# V01.net
KiCad netlist of a schematic drawn in Altium Designer
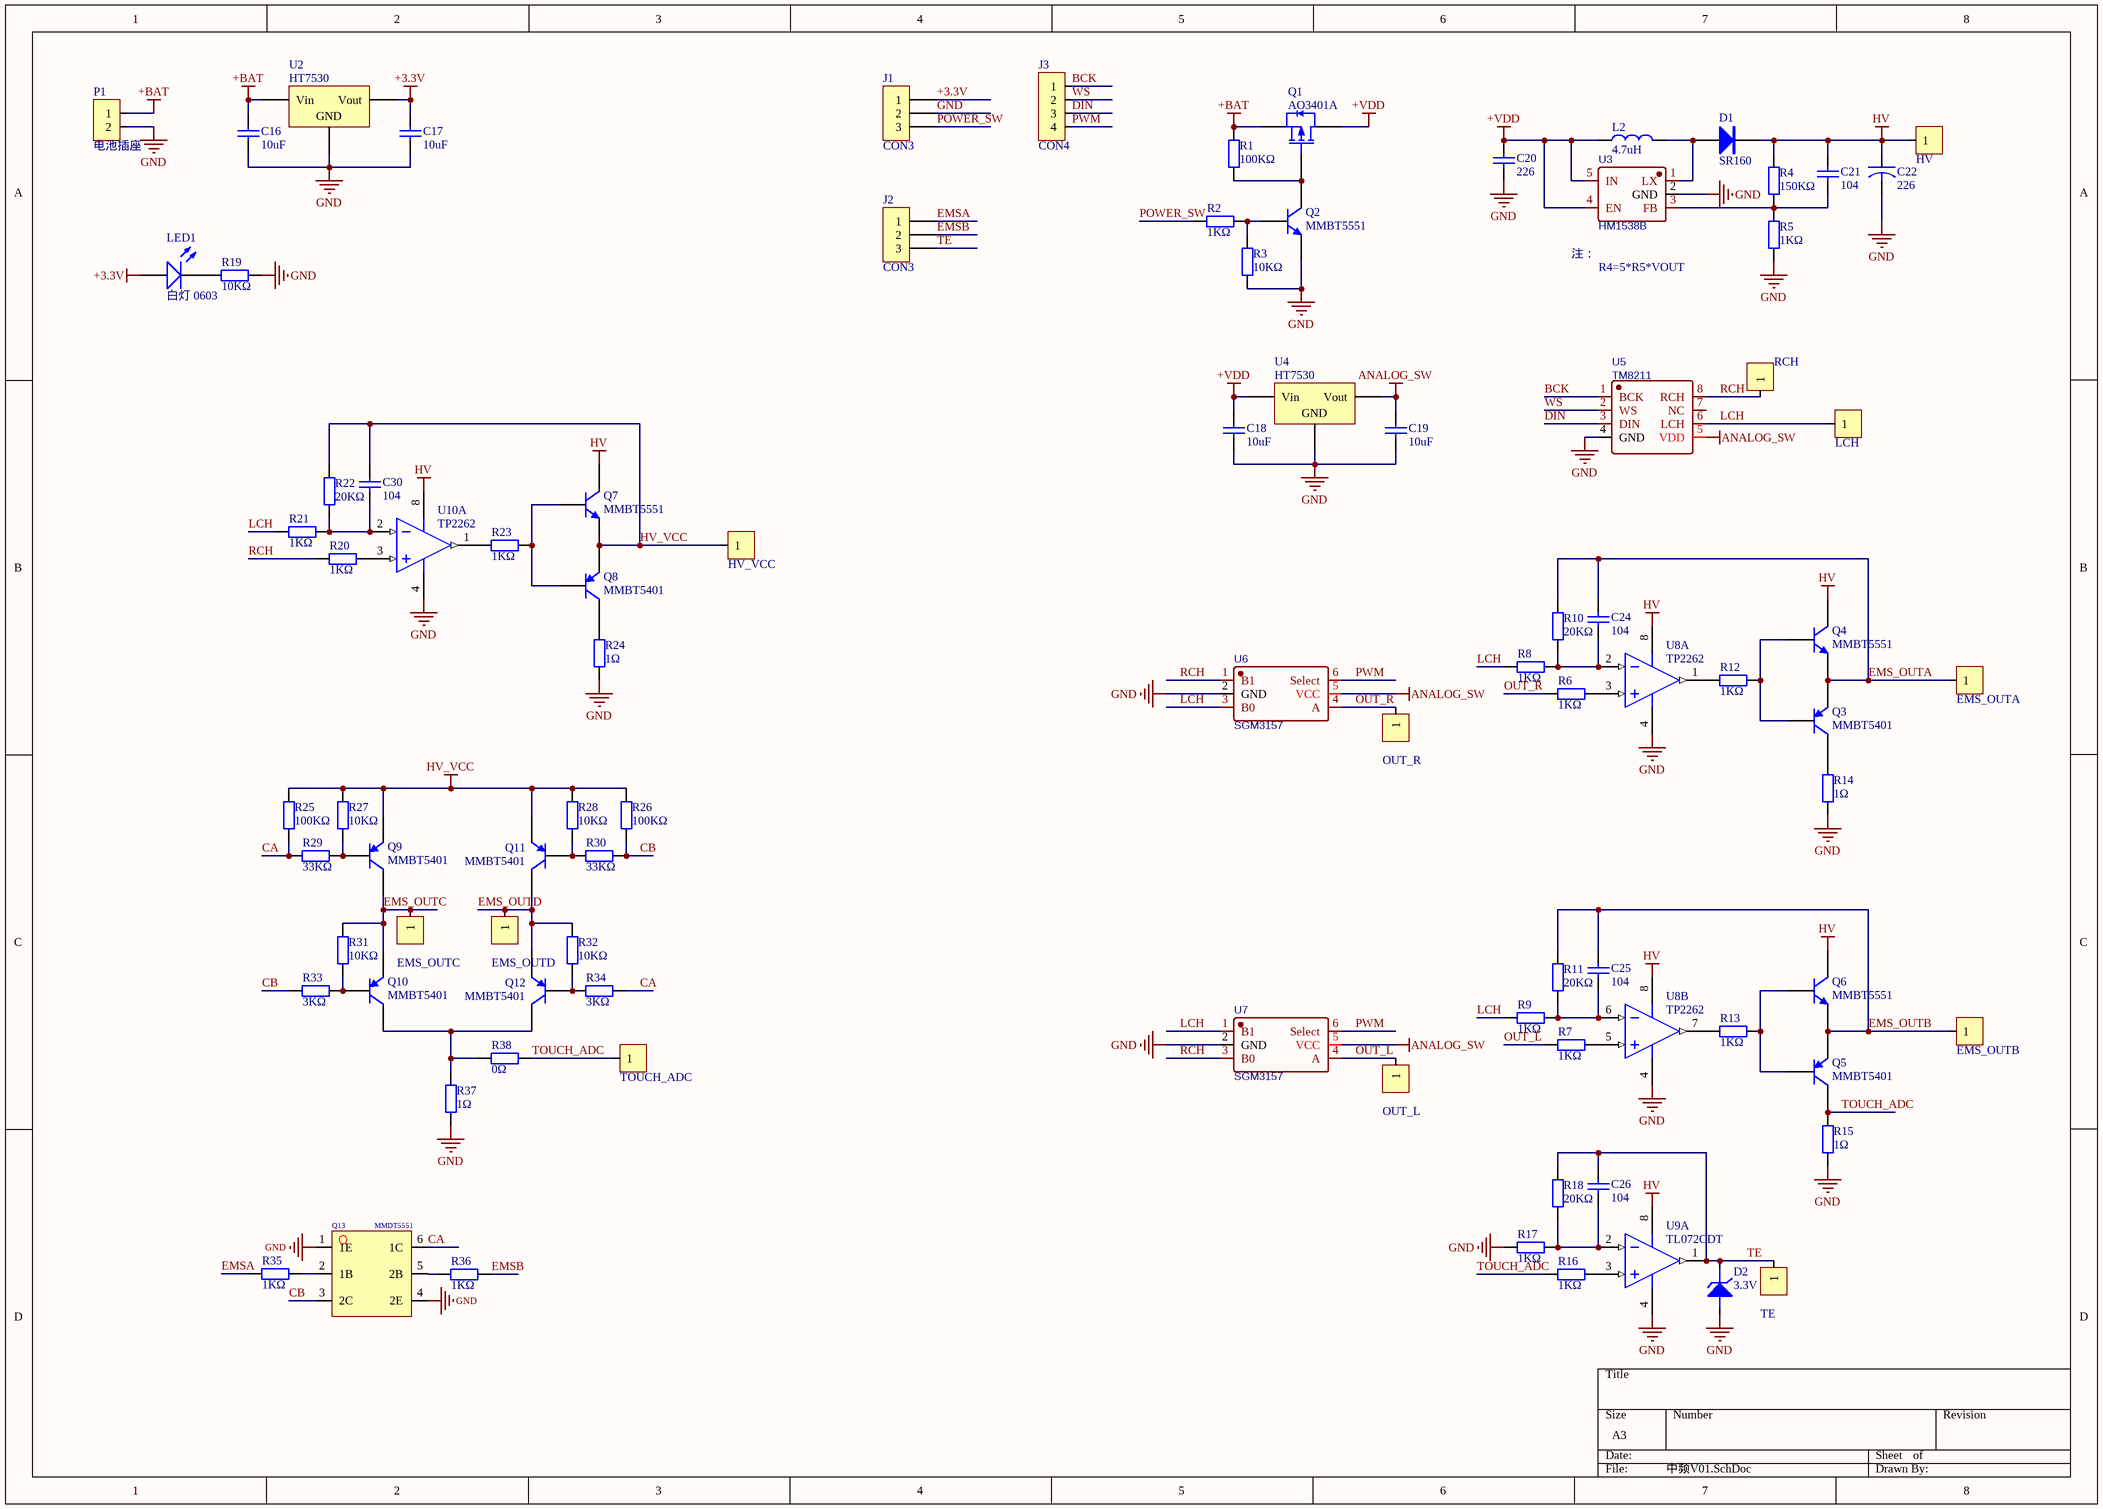
[diagram p0: 中频V01.SchDoc]

(export (version "E")
  (design (tool "Eeschema 10.0.6"))
  (components
    (comp (ref "C16")
      (value "10uF")
      (footprint "0603_C")
      (description "贴片电容")
      (libsource (lib "Cap") (part "0603 1.2nF (122) 10% 50V"))
    )
    (comp (ref "C17")
      (value "10uF")
      (footprint "0603_C")
      (description "贴片电容")
      (libsource (lib "Cap") (part "0603 1.2nF (122) 10% 50V"))
    )
    (comp (ref "C18")
      (value "10uF")
      (footprint "0603_C")
      (description "贴片电容")
      (libsource (lib "Cap") (part "0603 1.2nF (122) 10% 50V"))
    )
    (comp (ref "C19")
      (value "10uF")
      (footprint "0603_C")
      (description "贴片电容")
      (libsource (lib "Cap") (part "0603 1.2nF (122) 10% 50V"))
    )
    (comp (ref "C20")
      (value "226")
      (footprint "0603_C")
      (description "贴片电容")
      (libsource (lib "Cap") (part "0603 1uF (105) 10% 50V"))
    )
    (comp (ref "C21")
      (value "104")
      (footprint "0603_C")
      (description "贴片电容")
      (libsource (lib "Cap") (part "0603 1uF (105) 10% 50V"))
    )
    (comp (ref "C22")
      (value "226")
      (footprint "1206_C")
      (description "Capacitor")
      (libsource (lib "原理图标准元件库") (part "CAPACITOR"))
    )
    (comp (ref "C24")
      (value "104")
      (footprint "0603_C")
      (description "贴片电容")
      (libsource (lib "Cap") (part "0603 1.2nF (122) 10% 50V"))
    )
    (comp (ref "C25")
      (value "104")
      (footprint "0603_C")
      (description "贴片电容")
      (libsource (lib "Cap") (part "0603 1.2nF (122) 10% 50V"))
    )
    (comp (ref "C26")
      (value "104")
      (footprint "0603_C")
      (description "贴片电容")
      (libsource (lib "Cap") (part "0603 1.2nF (122) 10% 50V"))
    )
    (comp (ref "C30")
      (value "104")
      (footprint "0603_C")
      (description "贴片电容")
      (libsource (lib "Cap") (part "0603 1.2nF (122) 10% 50V"))
    )
    (comp (ref "D1") (value "SR160") (footprint "SOD-123") (libsource (lib "XIONG190817") (part "DO")))
    (comp (ref "D2")
      (value "3.3V")
      (footprint "SOD-323")
      (description "Zener Diode")
      (libsource (lib "原理图标准元件库") (part "ZENER3"))
    )
    (comp (ref "EMS_OUTA")
      (value "CON1")
      (footprint "PAD-1P")
      (description "Connector")
      (libsource (lib "") (part "CON1_1"))
    )
    (comp (ref "EMS_OUTB")
      (value "CON1")
      (footprint "PAD-1P")
      (description "Connector")
      (libsource (lib "") (part "CON1_1"))
    )
    (comp (ref "EMS_OUTC")
      (value "CON1")
      (footprint "PAD-1P")
      (description "Connector")
      (libsource (lib "原理图标准元件库") (part "CON1"))
    )
    (comp (ref "EMS_OUTD")
      (value "CON1")
      (footprint "PAD-1P")
      (description "Connector")
      (libsource (lib "原理图标准元件库") (part "CON1"))
    )
    (comp (ref "HV")
      (value "CON1")
      (footprint "PAD-1P")
      (description "Connector")
      (libsource (lib "") (part "CON1_1"))
    )
    (comp (ref "HV_VCC")
      (value "CON1")
      (footprint "PAD-1P")
      (description "Connector")
      (libsource (lib "") (part "CON1_1"))
    )
    (comp (ref "J1")
      (value "CON3")
      (footprint "HDR-TH_3P-P2.54-V")
      (description "Connector")
      (libsource (lib "原理图标准元件库") (part "CON3"))
    )
    (comp (ref "J2")
      (value "CON3")
      (footprint "HDR-TH_3P-P2.54-V")
      (description "Connector")
      (libsource (lib "原理图标准元件库") (part "CON3"))
    )
    (comp (ref "J3")
      (value "CON4")
      (footprint "HDR-TH_4P-P2.54-V")
      (description "Connector")
      (libsource (lib "原理图标准元件库") (part "CON4"))
    )
    (comp (ref "L2") (value "4.7uH") (footprint "CD43") (libsource (lib "XIONG190817") (part "INDUCTOR")))
    (comp (ref "LCH")
      (value "CON1")
      (footprint "PAD-1P")
      (description "Connector")
      (libsource (lib "") (part "CON1_1"))
    )
    (comp (ref "LED1")
      (value "白灯 0603")
      (footprint "0603_LED_S1")
      (description "发光二极管")
      (libsource (lib "LED") (part "0603 白灯"))
    )
    (comp (ref "OUT_L")
      (value "CON1")
      (footprint "PAD-1P")
      (description "Connector")
      (libsource (lib "原理图标准元件库") (part "CON1"))
    )
    (comp (ref "OUT_R")
      (value "CON1")
      (footprint "PAD-1P")
      (description "Connector")
      (libsource (lib "原理图标准元件库") (part "CON1"))
    )
    (comp (ref "P1")
      (value "电池插座")
      (footprint "1.25-2PIN")
      (description "Connector")
      (libsource (lib "原理图标准元件库") (part "CON2"))
    )
    (comp (ref "Q1")
      (value "AO3401A")
      (footprint "SOT-23-3L")
      (description "MOS(场效应管)")
      (libsource (lib "MOS") (part "AO3401A P道沟 X13A15 SOT-23"))
    )
    (comp (ref "Q2")
      (value "MMBT5551")
      (footprint "SOT-23(SOT-23-3)")
      (description "三极管")
      (libsource (lib "Transistor_NPN") (part "SOT-23 MMBT5551  G1"))
    )
    (comp (ref "Q3")
      (value "MMBT5401")
      (footprint "SOT-23(SOT-23-3)")
      (description "三极管")
      (libsource (lib "Transistor_PNP") (part "SOT-23 MMBT5401 2L"))
    )
    (comp (ref "Q4")
      (value "MMBT5551")
      (footprint "SOT-23(SOT-23-3)")
      (description "三极管")
      (libsource (lib "Transistor_NPN") (part "SOT-23 MMBT5551  G1"))
    )
    (comp (ref "Q5")
      (value "MMBT5401")
      (footprint "SOT-23(SOT-23-3)")
      (description "三极管")
      (libsource (lib "Transistor_PNP") (part "SOT-23 MMBT5401 2L"))
    )
    (comp (ref "Q6")
      (value "MMBT5551")
      (footprint "SOT-23(SOT-23-3)")
      (description "三极管")
      (libsource (lib "Transistor_NPN") (part "SOT-23 MMBT5551  G1"))
    )
    (comp (ref "Q7")
      (value "MMBT5551")
      (footprint "SOT-23(SOT-23-3)")
      (description "三极管")
      (libsource (lib "Transistor_NPN") (part "SOT-23 MMBT5551  G1"))
    )
    (comp (ref "Q8")
      (value "MMBT5401")
      (footprint "SOT-23(SOT-23-3)")
      (description "三极管")
      (libsource (lib "Transistor_PNP") (part "SOT-23 MMBT5401 2L"))
    )
    (comp (ref "Q9")
      (value "MMBT5401")
      (footprint "SOT-23(SOT-23-3)")
      (description "三极管")
      (libsource (lib "Transistor_PNP") (part "SOT-23 MMBT5401 2L"))
    )
    (comp (ref "Q10")
      (value "MMBT5401")
      (footprint "SOT-23(SOT-23-3)")
      (description "三极管")
      (libsource (lib "Transistor_PNP") (part "SOT-23 MMBT5401 2L"))
    )
    (comp (ref "Q11")
      (value "MMBT5401")
      (footprint "SOT-23(SOT-23-3)")
      (description "三极管")
      (libsource (lib "Transistor_PNP") (part "SOT-23 MMBT5401 2L"))
    )
    (comp (ref "Q12")
      (value "MMBT5401")
      (footprint "SOT-23(SOT-23-3)")
      (description "三极管")
      (libsource (lib "Transistor_PNP") (part "SOT-23 MMBT5401 2L"))
    )
    (comp (ref "Q13") (value "MMDT5551") (footprint "SOT-363") (libsource (lib "宋德一自画库") (part "MMDT5551")))
    (comp (ref "R1")
      (value "100KΩ")
      (footprint "0603_R")
      (description "贴片电阻")
      (libsource (lib "") (part "0603 1.2KΩ (1201) 1%_3"))
    )
    (comp (ref "R2")
      (value "1KΩ")
      (footprint "0603_R")
      (description "贴片电阻")
      (libsource (lib "") (part "0603 1.2KΩ (1201) 1%_2"))
    )
    (comp (ref "R3")
      (value "10KΩ")
      (footprint "0603_R")
      (description "贴片电阻")
      (libsource (lib "") (part "0603 1.2KΩ (1201) 1%_1"))
    )
    (comp (ref "R4")
      (value "150KΩ")
      (footprint "0603_R")
      (description "贴片电阻")
      (libsource (lib "") (part "0603 1.2KΩ (1201) 1%_1"))
    )
    (comp (ref "R5")
      (value "1KΩ")
      (footprint "0603_R")
      (description "贴片电阻")
      (libsource (lib "") (part "0603 1.2KΩ (1201) 1%_1"))
    )
    (comp (ref "R6")
      (value "1KΩ")
      (footprint "0603_R")
      (description "贴片电阻")
      (libsource (lib "RES") (part "0603 1.2KΩ (1201) 1%"))
    )
    (comp (ref "R7")
      (value "1KΩ")
      (footprint "0603_R")
      (description "贴片电阻")
      (libsource (lib "RES") (part "0603 1.2KΩ (1201) 1%"))
    )
    (comp (ref "R8")
      (value "1KΩ")
      (footprint "0603_R")
      (description "贴片电阻")
      (libsource (lib "RES") (part "0603 1.2KΩ (1201) 1%"))
    )
    (comp (ref "R9")
      (value "1KΩ")
      (footprint "0603_R")
      (description "贴片电阻")
      (libsource (lib "RES") (part "0603 1.2KΩ (1201) 1%"))
    )
    (comp (ref "R10")
      (value "20KΩ")
      (footprint "0603_R")
      (description "贴片电阻")
      (libsource (lib "") (part "0603 1.2KΩ (1201) 1%_3"))
    )
    (comp (ref "R11")
      (value "20KΩ")
      (footprint "0603_R")
      (description "贴片电阻")
      (libsource (lib "") (part "0603 1.2KΩ (1201) 1%_1"))
    )
    (comp (ref "R12")
      (value "1KΩ")
      (footprint "0603_R")
      (description "贴片电阻")
      (libsource (lib "RES") (part "0603 1.2KΩ (1201) 1%"))
    )
    (comp (ref "R13")
      (value "1KΩ")
      (footprint "0603_R")
      (description "贴片电阻")
      (libsource (lib "RES") (part "0603 1.2KΩ (1201) 1%"))
    )
    (comp (ref "R14")
      (value "1Ω")
      (footprint "0603_R")
      (description "贴片电阻")
      (libsource (lib "") (part "0603 1.2KΩ (1201) 1%_1"))
    )
    (comp (ref "R15")
      (value "1Ω")
      (footprint "0603_R")
      (description "贴片电阻")
      (libsource (lib "") (part "0603 1.2KΩ (1201) 1%_1"))
    )
    (comp (ref "R16")
      (value "1KΩ")
      (footprint "0603_R")
      (description "贴片电阻")
      (libsource (lib "RES") (part "0603 1.2KΩ (1201) 1%"))
    )
    (comp (ref "R17")
      (value "1KΩ")
      (footprint "0603_R")
      (description "贴片电阻")
      (libsource (lib "RES") (part "0603 1.2KΩ (1201) 1%"))
    )
    (comp (ref "R18")
      (value "20KΩ")
      (footprint "0603_R")
      (description "贴片电阻")
      (libsource (lib "") (part "0603 1.2KΩ (1201) 1%_3"))
    )
    (comp (ref "R19")
      (value "10KΩ")
      (footprint "0603_R")
      (description "贴片电阻")
      (libsource (lib "") (part "0603 1.2KΩ (1201) 1%_2"))
    )
    (comp (ref "R20")
      (value "1KΩ")
      (footprint "0603_R")
      (description "贴片电阻")
      (libsource (lib "RES") (part "0603 1.2KΩ (1201) 1%"))
    )
    (comp (ref "R21")
      (value "1KΩ")
      (footprint "0603_R")
      (description "贴片电阻")
      (libsource (lib "RES") (part "0603 1.2KΩ (1201) 1%"))
    )
    (comp (ref "R22")
      (value "20KΩ")
      (footprint "0603_R")
      (description "贴片电阻")
      (libsource (lib "") (part "0603 1.2KΩ (1201) 1%_3"))
    )
    (comp (ref "R23")
      (value "1KΩ")
      (footprint "0603_R")
      (description "贴片电阻")
      (libsource (lib "RES") (part "0603 1.2KΩ (1201) 1%"))
    )
    (comp (ref "R24")
      (value "1Ω")
      (footprint "0603_R")
      (description "贴片电阻")
      (libsource (lib "") (part "0603 1.2KΩ (1201) 1%_1"))
    )
    (comp (ref "R25")
      (value "100KΩ")
      (footprint "0603_R")
      (description "贴片电阻")
      (libsource (lib "") (part "0603 1.2KΩ (1201) 1%_3"))
    )
    (comp (ref "R26")
      (value "100KΩ")
      (footprint "0603_R")
      (description "贴片电阻")
      (libsource (lib "") (part "0603 1.2KΩ (1201) 1%_3"))
    )
    (comp (ref "R27")
      (value "10KΩ")
      (footprint "0603_R")
      (description "贴片电阻")
      (libsource (lib "") (part "0603 1.2KΩ (1201) 1%_3"))
    )
    (comp (ref "R28")
      (value "10KΩ")
      (footprint "0603_R")
      (description "贴片电阻")
      (libsource (lib "") (part "0603 1.2KΩ (1201) 1%_3"))
    )
    (comp (ref "R29")
      (value "33KΩ")
      (footprint "0603_R")
      (description "贴片电阻")
      (libsource (lib "RES") (part "0603 1.2KΩ (1201) 1%"))
    )
    (comp (ref "R30")
      (value "33KΩ")
      (footprint "0603_R")
      (description "贴片电阻")
      (libsource (lib "RES") (part "0603 1.2KΩ (1201) 1%"))
    )
    (comp (ref "R31")
      (value "10KΩ")
      (footprint "0603_R")
      (description "贴片电阻")
      (libsource (lib "") (part "0603 1.2KΩ (1201) 1%_3"))
    )
    (comp (ref "R32")
      (value "10KΩ")
      (footprint "0603_R")
      (description "贴片电阻")
      (libsource (lib "") (part "0603 1.2KΩ (1201) 1%_3"))
    )
    (comp (ref "R33")
      (value "3KΩ")
      (footprint "0603_R")
      (description "贴片电阻")
      (libsource (lib "RES") (part "0603 1.2KΩ (1201) 1%"))
    )
    (comp (ref "R34")
      (value "3KΩ")
      (footprint "0603_R")
      (description "贴片电阻")
      (libsource (lib "RES") (part "0603 1.2KΩ (1201) 1%"))
    )
    (comp (ref "R35")
      (value "1KΩ")
      (footprint "0603_R")
      (description "贴片电阻")
      (libsource (lib "RES") (part "0603 1.2KΩ (1201) 1%"))
    )
    (comp (ref "R36")
      (value "1KΩ")
      (footprint "0603_R")
      (description "贴片电阻")
      (libsource (lib "RES") (part "0603 1.2KΩ (1201) 1%"))
    )
    (comp (ref "R37")
      (value "1Ω")
      (footprint "0603_R")
      (description "贴片电阻")
      (libsource (lib "") (part "0603 1.2KΩ (1201) 1%_1"))
    )
    (comp (ref "R38")
      (value "0Ω")
      (footprint "0603_R")
      (description "贴片电阻")
      (libsource (lib "RES") (part "0603 1.2KΩ (1201) 1%"))
    )
    (comp (ref "RCH")
      (value "CON1")
      (footprint "PAD-1P")
      (description "Connector")
      (libsource (lib "") (part "CON1_2"))
    )
    (comp (ref "TE")
      (value "CON1")
      (footprint "PAD-1P")
      (description "Connector")
      (libsource (lib "原理图标准元件库") (part "CON1"))
    )
    (comp (ref "TOUCH_ADC")
      (value "CON1")
      (footprint "PAD-1P")
      (description "Connector")
      (libsource (lib "") (part "CON1_1"))
    )
    (comp (ref "U2")
      (value "HT7530")
      (footprint "SOT-89(SOT-89-3)")
      (description "低压差线性稳压(LDO)")
      (libsource (lib "LDO") (part "SOT-89 HT7533-1"))
    )
    (comp (ref "U3")
      (value "HM1538B")
      (footprint "HM1538B")
      (fields
        (field (name "BOM_SUPPLIER PART") "C370888")
        (field (name "BOM_MANUFACTURER PART") "RY3750")
        (field (name "CONTRIBUTOR") "LCSC")
      )
      (libsource (lib "XIONG190817") (part "HM1538B"))
    )
    (comp (ref "U4")
      (value "HT7530")
      (footprint "SOT-89(SOT-89-3)")
      (description "低压差线性稳压(LDO)")
      (libsource (lib "LDO") (part "SOT-89 HT7533-1"))
    )
    (comp (ref "U5")
      (value "TM8211")
      (footprint "SOP-8_150MIL")
      (fields (field (name "BOM_SUPPLIER PART") "C92003"))
      (libsource (lib "XIONG190817") (part "TM8211"))
    )
    (comp (ref "U6")
      (value "SGM3157")
      (footprint "SC-70-6_L2.2-W1.3-P0.65-LS2.2-BL")
      (fields (field (name "BOM_SUPPLIER PART") "C394901") (field (name "CONTRIBUTOR") "LCSC"))
      (libsource (lib "XIONG190817") (part "SGM3157"))
    )
    (comp (ref "U7")
      (value "SGM3157")
      (footprint "SC-70-6_L2.2-W1.3-P0.65-LS2.2-BL")
      (fields (field (name "BOM_SUPPLIER PART") "C394901") (field (name "CONTRIBUTOR") "LCSC"))
      (libsource (lib "XIONG190817") (part "SGM3157"))
    )
    (comp (ref "U8")
      (value "TP2262")
      (footprint "SOIC-8_150mil")
      (description "运放")
      (libsource (lib "Miscellaneous Devices LC") (part "TL072CDT_[C6961]"))
    )
    (comp (ref "U9")
      (value "TL072CDT")
      (footprint "SOIC-8_150mil")
      (description "运放")
      (libsource (lib "Miscellaneous Devices LC") (part "TL072CDT_[C6961]"))
    )
    (comp (ref "U10")
      (value "TP2262")
      (footprint "SOIC-8_150mil")
      (description "运放")
      (libsource (lib "Miscellaneous Devices LC") (part "TL072CDT_[C6961]"))
    )
  )
  (nets
    (net (code "1") (name "+3.3V") (class "Default")
      (node (ref "C17") (pin "2") (pinfunction "2_2") (pintype "passive"))
      (node (ref "J1") (pin "1") (pinfunction "1_1") (pintype "passive"))
      (node (ref "LED1") (pin "A") (pinfunction "A_A") (pintype "passive"))
      (node (ref "U2") (pin "3") (pinfunction "Vout_3") (pintype "passive"))
    )
    (net (code "2") (name "+BAT") (class "Default")
      (node (ref "C16") (pin "2") (pinfunction "2_2") (pintype "passive"))
      (node (ref "P1") (pin "1") (pinfunction "1_1") (pintype "passive"))
      (node (ref "Q1") (pin "2") (pinfunction "S_2") (pintype "passive"))
      (node (ref "R1") (pin "2") (pinfunction "2_2") (pintype "passive"))
      (node (ref "U2") (pin "2") (pinfunction "Vin_2") (pintype "passive"))
    )
    (net (code "3") (name "+VDD") (class "Default")
      (node (ref "C18") (pin "2") (pinfunction "2_2") (pintype "passive"))
      (node (ref "C20") (pin "2") (pinfunction "2_2") (pintype "passive"))
      (node (ref "L2") (pin "2") (pinfunction "2_2") (pintype "passive"))
      (node (ref "Q1") (pin "3") (pinfunction "D_3") (pintype "passive"))
      (node (ref "U3") (pin "4") (pinfunction "EN_4") (pintype "passive"))
      (node (ref "U3") (pin "5") (pinfunction "IN_5") (pintype "passive"))
      (node (ref "U4") (pin "2") (pinfunction "Vin_2") (pintype "passive"))
    )
    (net (code "4") (name "/BCK") (class "Default")
      (node (ref "J3") (pin "1") (pinfunction "1_1") (pintype "passive"))
      (node (ref "U5") (pin "1") (pinfunction "BCK_1") (pintype "passive"))
    )
    (net (code "5") (name "/CA") (class "Default")
      (node (ref "Q13") (pin "6") (pinfunction "1C_6") (pintype "passive"))
      (node (ref "R25") (pin "1") (pinfunction "1_1") (pintype "passive"))
      (node (ref "R29") (pin "1") (pinfunction "1_1") (pintype "passive"))
      (node (ref "R34") (pin "2") (pinfunction "2_2") (pintype "passive"))
    )
    (net (code "6") (name "/CB") (class "Default")
      (node (ref "Q13") (pin "3") (pinfunction "2C_3") (pintype "passive"))
      (node (ref "R26") (pin "1") (pinfunction "1_1") (pintype "passive"))
      (node (ref "R30") (pin "2") (pinfunction "2_2") (pintype "passive"))
      (node (ref "R33") (pin "1") (pinfunction "1_1") (pintype "passive"))
    )
    (net (code "7") (name "/DIN") (class "Default")
      (node (ref "J3") (pin "3") (pinfunction "3_3") (pintype "passive"))
      (node (ref "U5") (pin "3") (pinfunction "DIN_3") (pintype "passive"))
    )
    (net (code "8") (name "/EMSA") (class "Default")
      (node (ref "J2") (pin "1") (pinfunction "1_1") (pintype "passive"))
      (node (ref "R35") (pin "1") (pinfunction "1_1") (pintype "passive"))
    )
    (net (code "9") (name "/EMSB") (class "Default")
      (node (ref "J2") (pin "2") (pinfunction "2_2") (pintype "passive"))
      (node (ref "R36") (pin "2") (pinfunction "2_2") (pintype "passive"))
    )
    (net (code "10") (name "/EMS_OUTA") (class "Default")
      (node (ref "C24") (pin "2") (pinfunction "2_2") (pintype "passive"))
      (node (ref "EMS_OUTA") (pin "1") (pinfunction "1_1") (pintype "passive"))
      (node (ref "Q3") (pin "2") (pinfunction "E_2") (pintype "passive"))
      (node (ref "Q4") (pin "2") (pinfunction "E_2") (pintype "passive"))
      (node (ref "R10") (pin "2") (pinfunction "2_2") (pintype "passive"))
    )
    (net (code "11") (name "/EMS_OUTB") (class "Default")
      (node (ref "C25") (pin "2") (pinfunction "2_2") (pintype "passive"))
      (node (ref "EMS_OUTB") (pin "1") (pinfunction "1_1") (pintype "passive"))
      (node (ref "Q5") (pin "2") (pinfunction "E_2") (pintype "passive"))
      (node (ref "Q6") (pin "2") (pinfunction "E_2") (pintype "passive"))
      (node (ref "R11") (pin "1") (pinfunction "1_1") (pintype "passive"))
    )
    (net (code "12") (name "/EMS_OUTC") (class "Default")
      (node (ref "EMS_OUTC") (pin "1") (pinfunction "1_1") (pintype "passive"))
      (node (ref "Q10") (pin "2") (pinfunction "E_2") (pintype "passive"))
      (node (ref "Q9") (pin "3") (pinfunction "C_3") (pintype "passive"))
      (node (ref "R31") (pin "2") (pinfunction "2_2") (pintype "passive"))
    )
    (net (code "13") (name "/EMS_OUTD") (class "Default")
      (node (ref "EMS_OUTD") (pin "1") (pinfunction "1_1") (pintype "passive"))
      (node (ref "Q11") (pin "3") (pinfunction "C_3") (pintype "passive"))
      (node (ref "Q12") (pin "2") (pinfunction "E_2") (pintype "passive"))
      (node (ref "R32") (pin "2") (pinfunction "2_2") (pintype "passive"))
    )
    (net (code "14") (name "/LCH") (class "Default")
      (node (ref "LCH") (pin "1") (pinfunction "1_1") (pintype "passive"))
      (node (ref "R21") (pin "1") (pinfunction "1_1") (pintype "passive"))
      (node (ref "R8") (pin "1") (pinfunction "1_1") (pintype "passive"))
      (node (ref "R9") (pin "1") (pinfunction "1_1") (pintype "passive"))
      (node (ref "U5") (pin "6") (pinfunction "LCH_6") (pintype "passive"))
      (node (ref "U6") (pin "3") (pinfunction "B0_3") (pintype "passive"))
      (node (ref "U7") (pin "1") (pinfunction "B1_1") (pintype "passive"))
    )
    (net (code "15") (name "/OUT_L") (class "Default")
      (node (ref "OUT_L") (pin "1") (pinfunction "1_1") (pintype "passive"))
      (node (ref "R7") (pin "1") (pinfunction "1_1") (pintype "passive"))
      (node (ref "U7") (pin "4") (pinfunction "A_4") (pintype "passive"))
    )
    (net (code "16") (name "/OUT_R") (class "Default")
      (node (ref "OUT_R") (pin "1") (pinfunction "1_1") (pintype "passive"))
      (node (ref "R6") (pin "1") (pinfunction "1_1") (pintype "passive"))
      (node (ref "U6") (pin "4") (pinfunction "A_4") (pintype "passive"))
    )
    (net (code "17") (name "/POWER_SW") (class "Default")
      (node (ref "J1") (pin "3") (pinfunction "3_3") (pintype "passive"))
      (node (ref "R2") (pin "2") (pinfunction "2_2") (pintype "passive"))
    )
    (net (code "18") (name "/PWM") (class "Default")
      (node (ref "J3") (pin "4") (pinfunction "4_4") (pintype "passive"))
      (node (ref "U6") (pin "6") (pinfunction "Select_6") (pintype "passive"))
      (node (ref "U7") (pin "6") (pinfunction "Select_6") (pintype "passive"))
    )
    (net (code "19") (name "/RCH") (class "Default")
      (node (ref "R20") (pin "1") (pinfunction "1_1") (pintype "passive"))
      (node (ref "RCH") (pin "1") (pinfunction "1_1") (pintype "passive"))
      (node (ref "U5") (pin "8") (pinfunction "RCH_8") (pintype "passive"))
      (node (ref "U6") (pin "1") (pinfunction "B1_1") (pintype "passive"))
      (node (ref "U7") (pin "3") (pinfunction "B0_3") (pintype "passive"))
    )
    (net (code "20") (name "/TE") (class "Default")
      (node (ref "C26") (pin "2") (pinfunction "2_2") (pintype "passive"))
      (node (ref "D2") (pin "2") (pinfunction "K_2") (pintype "passive"))
      (node (ref "J2") (pin "3") (pinfunction "3_3") (pintype "passive"))
      (node (ref "R18") (pin "2") (pinfunction "2_2") (pintype "passive"))
      (node (ref "TE") (pin "1") (pinfunction "1_1") (pintype "passive"))
      (node (ref "U9") (pin "1") (pinfunction "OUT_1") (pintype "output"))
    )
    (net (code "21") (name "/TOUCH_ADC") (class "Default")
      (node (ref "Q5") (pin "3") (pinfunction "C_3") (pintype "passive"))
      (node (ref "R15") (pin "1") (pinfunction "1_1") (pintype "passive"))
      (node (ref "R16") (pin "1") (pinfunction "1_1") (pintype "passive"))
      (node (ref "R38") (pin "2") (pinfunction "2_2") (pintype "passive"))
      (node (ref "TOUCH_ADC") (pin "1") (pinfunction "1_1") (pintype "passive"))
    )
    (net (code "22") (name "/WS") (class "Default")
      (node (ref "J3") (pin "2") (pinfunction "2_2") (pintype "passive"))
      (node (ref "U5") (pin "2") (pinfunction "WS_2") (pintype "passive"))
    )
    (net (code "23") (name "ANALOG_SW") (class "Default")
      (node (ref "C19") (pin "2") (pinfunction "2_2") (pintype "passive"))
      (node (ref "U4") (pin "3") (pinfunction "Vout_3") (pintype "passive"))
      (node (ref "U5") (pin "5") (pinfunction "VDD_5") (pintype "passive"))
      (node (ref "U6") (pin "5") (pinfunction "VCC_5") (pintype "passive"))
      (node (ref "U7") (pin "5") (pinfunction "VCC_5") (pintype "passive"))
    )
    (net (code "24") (name "GND") (class "Default")
      (node (ref "C16") (pin "1") (pinfunction "1_1") (pintype "passive"))
      (node (ref "C17") (pin "1") (pinfunction "1_1") (pintype "passive"))
      (node (ref "C18") (pin "1") (pinfunction "1_1") (pintype "passive"))
      (node (ref "C19") (pin "1") (pinfunction "1_1") (pintype "passive"))
      (node (ref "C20") (pin "1") (pinfunction "1_1") (pintype "passive"))
      (node (ref "C22") (pin "2") (pinfunction "2_2") (pintype "passive"))
      (node (ref "D2") (pin "1") (pinfunction "A_1") (pintype "passive"))
      (node (ref "J1") (pin "2") (pinfunction "2_2") (pintype "passive"))
      (node (ref "P1") (pin "2") (pinfunction "2_2") (pintype "passive"))
      (node (ref "Q13") (pin "1") (pinfunction "1E_1") (pintype "passive"))
      (node (ref "Q13") (pin "4") (pinfunction "2E_4") (pintype "passive"))
      (node (ref "Q2") (pin "2") (pinfunction "E_2") (pintype "passive"))
      (node (ref "R14") (pin "2") (pinfunction "2_2") (pintype "passive"))
      (node (ref "R15") (pin "2") (pinfunction "2_2") (pintype "passive"))
      (node (ref "R17") (pin "1") (pinfunction "1_1") (pintype "passive"))
      (node (ref "R19") (pin "1") (pinfunction "1_1") (pintype "passive"))
      (node (ref "R24") (pin "2") (pinfunction "2_2") (pintype "passive"))
      (node (ref "R3") (pin "2") (pinfunction "2_2") (pintype "passive"))
      (node (ref "R37") (pin "2") (pinfunction "2_2") (pintype "passive"))
      (node (ref "R5") (pin "2") (pinfunction "2_2") (pintype "passive"))
      (node (ref "U10") (pin "4") (pinfunction "V-_4") (pintype "power_in"))
      (node (ref "U2") (pin "1") (pinfunction "GND_1") (pintype "passive"))
      (node (ref "U3") (pin "2") (pinfunction "GND_2") (pintype "passive"))
      (node (ref "U4") (pin "1") (pinfunction "GND_1") (pintype "passive"))
      (node (ref "U5") (pin "4") (pinfunction "GND_4") (pintype "passive"))
      (node (ref "U6") (pin "2") (pinfunction "GND_2") (pintype "passive"))
      (node (ref "U7") (pin "2") (pinfunction "GND_2") (pintype "passive"))
      (node (ref "U8") (pin "4") (pinfunction "V-_4") (pintype "power_in"))
      (node (ref "U9") (pin "4") (pinfunction "V-_4") (pintype "power_in"))
    )
    (net (code "25") (name "HV") (class "Default")
      (node (ref "C21") (pin "2") (pinfunction "2_2") (pintype "passive"))
      (node (ref "C22") (pin "1") (pinfunction "1_1") (pintype "passive"))
      (node (ref "D1") (pin "2") (pinfunction "2_2") (pintype "passive"))
      (node (ref "HV") (pin "1") (pinfunction "1_1") (pintype "passive"))
      (node (ref "Q4") (pin "3") (pinfunction "C_3") (pintype "passive"))
      (node (ref "Q6") (pin "3") (pinfunction "C_3") (pintype "passive"))
      (node (ref "Q7") (pin "3") (pinfunction "C_3") (pintype "passive"))
      (node (ref "R4") (pin "1") (pinfunction "1_1") (pintype "passive"))
      (node (ref "U10") (pin "8") (pinfunction "V+_8") (pintype "power_in"))
      (node (ref "U8") (pin "8") (pinfunction "V+_8") (pintype "power_in"))
      (node (ref "U9") (pin "8") (pinfunction "V+_8") (pintype "power_in"))
    )
    (net (code "26") (name "HV_VCC") (class "Default")
      (node (ref "C30") (pin "2") (pinfunction "2_2") (pintype "passive"))
      (node (ref "HV_VCC") (pin "1") (pinfunction "1_1") (pintype "passive"))
      (node (ref "Q11") (pin "2") (pinfunction "E_2") (pintype "passive"))
      (node (ref "Q7") (pin "2") (pinfunction "E_2") (pintype "passive"))
      (node (ref "Q8") (pin "2") (pinfunction "E_2") (pintype "passive"))
      (node (ref "Q9") (pin "2") (pinfunction "E_2") (pintype "passive"))
      (node (ref "R22") (pin "2") (pinfunction "2_2") (pintype "passive"))
      (node (ref "R25") (pin "2") (pinfunction "2_2") (pintype "passive"))
      (node (ref "R26") (pin "2") (pinfunction "2_2") (pintype "passive"))
      (node (ref "R27") (pin "2") (pinfunction "2_2") (pintype "passive"))
      (node (ref "R28") (pin "2") (pinfunction "2_2") (pintype "passive"))
    )
    (net (code "27") (name "Net-(LED1-PadK)") (class "Default")
      (node (ref "LED1") (pin "K") (pinfunction "K_K") (pintype "passive"))
      (node (ref "R19") (pin "2") (pinfunction "2_2") (pintype "passive"))
    )
    (net (code "28") (name "Net-(Q1-G)") (class "Default")
      (node (ref "Q1") (pin "1") (pinfunction "G_1") (pintype "passive"))
      (node (ref "Q2") (pin "3") (pinfunction "C_3") (pintype "passive"))
      (node (ref "R1") (pin "1") (pinfunction "1_1") (pintype "passive"))
    )
    (net (code "29") (name "Net-(Q2-B)") (class "Default")
      (node (ref "Q2") (pin "1") (pinfunction "B_1") (pintype "passive"))
      (node (ref "R2") (pin "1") (pinfunction "1_1") (pintype "passive"))
      (node (ref "R3") (pin "1") (pinfunction "1_1") (pintype "passive"))
    )
    (net (code "30") (name "Net-(Q3-B)") (class "Default")
      (node (ref "Q3") (pin "1") (pinfunction "B_1") (pintype "passive"))
      (node (ref "Q4") (pin "1") (pinfunction "B_1") (pintype "passive"))
      (node (ref "R12") (pin "2") (pinfunction "2_2") (pintype "passive"))
    )
    (net (code "31") (name "Net-(Q3-C)") (class "Default")
      (node (ref "Q3") (pin "3") (pinfunction "C_3") (pintype "passive"))
      (node (ref "R14") (pin "1") (pinfunction "1_1") (pintype "passive"))
    )
    (net (code "32") (name "Net-(Q5-B)") (class "Default")
      (node (ref "Q5") (pin "1") (pinfunction "B_1") (pintype "passive"))
      (node (ref "Q6") (pin "1") (pinfunction "B_1") (pintype "passive"))
      (node (ref "R13") (pin "2") (pinfunction "2_2") (pintype "passive"))
    )
    (net (code "33") (name "Net-(Q7-B)") (class "Default")
      (node (ref "Q7") (pin "1") (pinfunction "B_1") (pintype "passive"))
      (node (ref "Q8") (pin "1") (pinfunction "B_1") (pintype "passive"))
      (node (ref "R23") (pin "2") (pinfunction "2_2") (pintype "passive"))
    )
    (net (code "34") (name "Net-(Q8-C)") (class "Default")
      (node (ref "Q8") (pin "3") (pinfunction "C_3") (pintype "passive"))
      (node (ref "R24") (pin "1") (pinfunction "1_1") (pintype "passive"))
    )
    (net (code "35") (name "Net-(Q9-B)") (class "Default")
      (node (ref "Q9") (pin "1") (pinfunction "B_1") (pintype "passive"))
      (node (ref "R27") (pin "1") (pinfunction "1_1") (pintype "passive"))
      (node (ref "R29") (pin "2") (pinfunction "2_2") (pintype "passive"))
    )
    (net (code "36") (name "Net-(Q10-B)") (class "Default")
      (node (ref "Q10") (pin "1") (pinfunction "B_1") (pintype "passive"))
      (node (ref "R31") (pin "1") (pinfunction "1_1") (pintype "passive"))
      (node (ref "R33") (pin "2") (pinfunction "2_2") (pintype "passive"))
    )
    (net (code "37") (name "Net-(Q10-C)") (class "Default")
      (node (ref "Q10") (pin "3") (pinfunction "C_3") (pintype "passive"))
      (node (ref "Q12") (pin "3") (pinfunction "C_3") (pintype "passive"))
      (node (ref "R37") (pin "1") (pinfunction "1_1") (pintype "passive"))
      (node (ref "R38") (pin "1") (pinfunction "1_1") (pintype "passive"))
    )
    (net (code "38") (name "Net-(Q11-B)") (class "Default")
      (node (ref "Q11") (pin "1") (pinfunction "B_1") (pintype "passive"))
      (node (ref "R28") (pin "1") (pinfunction "1_1") (pintype "passive"))
      (node (ref "R30") (pin "1") (pinfunction "1_1") (pintype "passive"))
    )
    (net (code "39") (name "Net-(Q12-B)") (class "Default")
      (node (ref "Q12") (pin "1") (pinfunction "B_1") (pintype "passive"))
      (node (ref "R32") (pin "1") (pinfunction "1_1") (pintype "passive"))
      (node (ref "R34") (pin "1") (pinfunction "1_1") (pintype "passive"))
    )
    (net (code "40") (name "Net-(Q13-1B)") (class "Default")
      (node (ref "Q13") (pin "2") (pinfunction "1B_2") (pintype "passive"))
      (node (ref "R35") (pin "2") (pinfunction "2_2") (pintype "passive"))
    )
    (net (code "41") (name "Net-(Q13-2B)") (class "Default")
      (node (ref "Q13") (pin "5") (pinfunction "2B_5") (pintype "passive"))
      (node (ref "R36") (pin "1") (pinfunction "1_1") (pintype "passive"))
    )
    (net (code "42") (name "Net-(U3-FB)") (class "Default")
      (node (ref "C21") (pin "1") (pinfunction "1_1") (pintype "passive"))
      (node (ref "R4") (pin "2") (pinfunction "2_2") (pintype "passive"))
      (node (ref "R5") (pin "1") (pinfunction "1_1") (pintype "passive"))
      (node (ref "U3") (pin "3") (pinfunction "FB_3") (pintype "passive"))
    )
    (net (code "43") (name "Net-(U3-LX)") (class "Default")
      (node (ref "D1") (pin "1") (pinfunction "1_1") (pintype "passive"))
      (node (ref "L2") (pin "1") (pinfunction "1_1") (pintype "passive"))
      (node (ref "U3") (pin "1") (pinfunction "LX_1") (pintype "passive"))
    )
    (net (code "44") (name "Net-(U8A-IN+)") (class "Default")
      (node (ref "R6") (pin "2") (pinfunction "2_2") (pintype "passive"))
      (node (ref "U8") (pin "3") (pinfunction "IN+_3") (pintype "input"))
    )
    (net (code "45") (name "Net-(U8A-IN-)") (class "Default")
      (node (ref "C24") (pin "1") (pinfunction "1_1") (pintype "passive"))
      (node (ref "R10") (pin "1") (pinfunction "1_1") (pintype "passive"))
      (node (ref "R8") (pin "2") (pinfunction "2_2") (pintype "passive"))
      (node (ref "U8") (pin "2") (pinfunction "IN-_2") (pintype "input"))
    )
    (net (code "46") (name "Net-(U8A-OUT)") (class "Default")
      (node (ref "R12") (pin "1") (pinfunction "1_1") (pintype "passive"))
      (node (ref "U8") (pin "1") (pinfunction "OUT_1") (pintype "output"))
    )
    (net (code "47") (name "Net-(U8B-IN+)") (class "Default")
      (node (ref "R7") (pin "2") (pinfunction "2_2") (pintype "passive"))
      (node (ref "U8") (pin "5") (pinfunction "IN+_5") (pintype "input"))
    )
    (net (code "48") (name "Net-(U8B-IN-)") (class "Default")
      (node (ref "C25") (pin "1") (pinfunction "1_1") (pintype "passive"))
      (node (ref "R11") (pin "2") (pinfunction "2_2") (pintype "passive"))
      (node (ref "R9") (pin "2") (pinfunction "2_2") (pintype "passive"))
      (node (ref "U8") (pin "6") (pinfunction "IN-_6") (pintype "input"))
    )
    (net (code "49") (name "Net-(U8B-OUT)") (class "Default")
      (node (ref "R13") (pin "1") (pinfunction "1_1") (pintype "passive"))
      (node (ref "U8") (pin "7") (pinfunction "OUT_7") (pintype "output"))
    )
    (net (code "50") (name "Net-(U9A-IN+)") (class "Default")
      (node (ref "R16") (pin "2") (pinfunction "2_2") (pintype "passive"))
      (node (ref "U9") (pin "3") (pinfunction "IN+_3") (pintype "input"))
    )
    (net (code "51") (name "Net-(U9A-IN-)") (class "Default")
      (node (ref "C26") (pin "1") (pinfunction "1_1") (pintype "passive"))
      (node (ref "R17") (pin "2") (pinfunction "2_2") (pintype "passive"))
      (node (ref "R18") (pin "1") (pinfunction "1_1") (pintype "passive"))
      (node (ref "U9") (pin "2") (pinfunction "IN-_2") (pintype "input"))
    )
    (net (code "52") (name "Net-(U10A-IN+)") (class "Default")
      (node (ref "R20") (pin "2") (pinfunction "2_2") (pintype "passive"))
      (node (ref "U10") (pin "3") (pinfunction "IN+_3") (pintype "input"))
    )
    (net (code "53") (name "Net-(U10A-IN-)") (class "Default")
      (node (ref "C30") (pin "1") (pinfunction "1_1") (pintype "passive"))
      (node (ref "R21") (pin "2") (pinfunction "2_2") (pintype "passive"))
      (node (ref "R22") (pin "1") (pinfunction "1_1") (pintype "passive"))
      (node (ref "U10") (pin "2") (pinfunction "IN-_2") (pintype "input"))
    )
    (net (code "54") (name "Net-(U10A-OUT)") (class "Default")
      (node (ref "R23") (pin "1") (pinfunction "1_1") (pintype "passive"))
      (node (ref "U10") (pin "1") (pinfunction "OUT_1") (pintype "output"))
    )
    (net (code "55") (name "unconnected-(U5-NC-Pad7)") (class "Default")
      (node (ref "U5") (pin "7") (pinfunction "NC_7") (pintype "passive"))
    )
  )
)
